# p1_main_ac_dc.net
KiCad netlist of a schematic drawn in Altium Designer
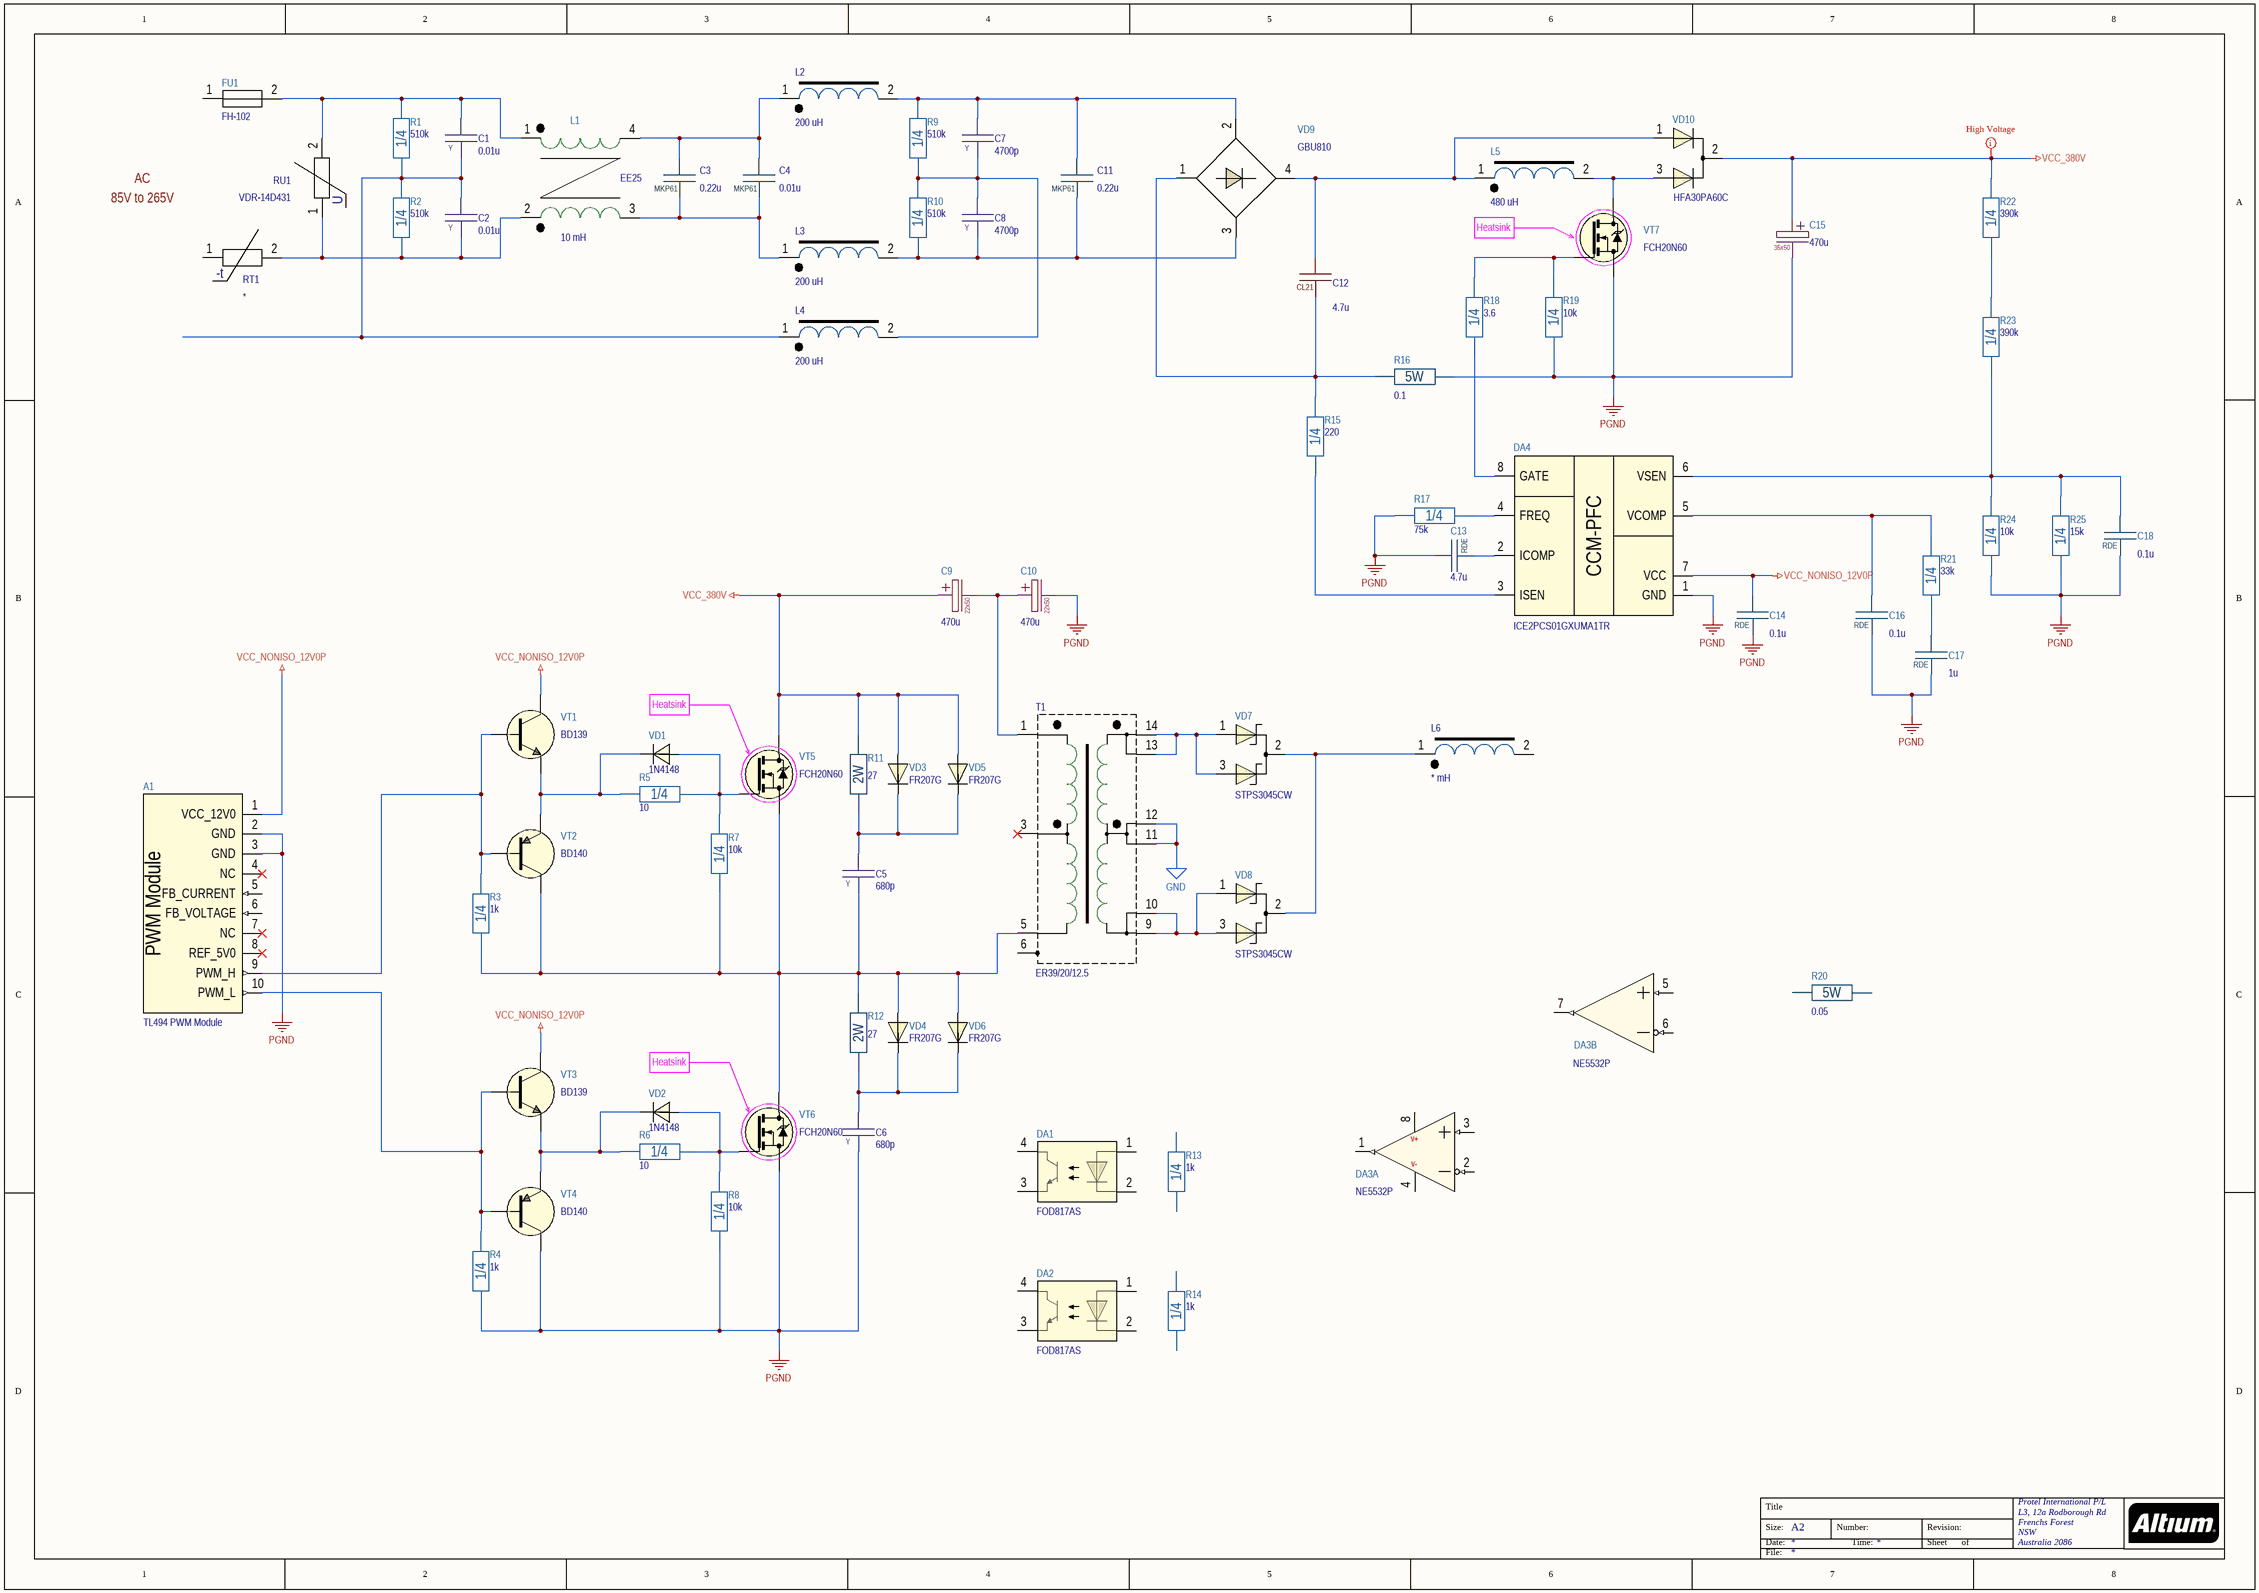
[diagram p0: p1_main_ac_dc.SchDoc]

(export (version "E")
  (design (tool "Eeschema 10.0.6"))
  (components
    (comp (ref "A1")
      (value "TL494 PWM Module")
      (footprint "PcbLib_Others:PWM-TL494")
      (libsource (lib "Schlib_OtherComponents") (part "PWM-MODULE"))
    )
    (comp (ref "C1")
      (value "0.01u")
      (footprint "PcbLib_RC:JYC_Y2_CAP_6.5")
      (description "High Voltage Ceramic Capacitor")
      (fields
        (field (name "TOLERANCE") "± 20 %")
        (field (name "VOLTAGE") "2000V")
        (field (name "PACKAGE") "Y")
      )
      (libsource (lib "Schlib_RC") (part "JB_Y2"))
    )
    (comp (ref "C2")
      (value "0.01u")
      (footprint "PcbLib_RC:JYC_Y2_CAP_6.5")
      (description "High Voltage Ceramic Capacitor")
      (fields
        (field (name "TOLERANCE") "± 20 %")
        (field (name "VOLTAGE") "2000V")
        (field (name "PACKAGE") "Y")
      )
      (libsource (lib "Schlib_RC") (part "JB_Y2"))
    )
    (comp (ref "C3")
      (value "0.22u")
      (footprint "PcbLib_RC:MKP61_18x14.5x8.5_P15")
      (description "Metallized Polypropylene Film Capacitor for high voltage application")
      (fields
        (field (name "TOLERANCE") "± 10 %")
        (field (name "VOLTAGE") "300V")
        (field (name "PACKAGE") "MKP61")
      )
      (libsource (lib "Schlib_RC") (part "MKP61"))
    )
    (comp (ref "C4")
      (value "0.01u")
      (footprint "PcbLib_RC:MKP61_18x12x6_P15")
      (description "Metallized Polypropylene Film Capacitor for high voltage application")
      (fields
        (field (name "TOLERANCE") "± 10 %")
        (field (name "VOLTAGE") "300V")
        (field (name "PACKAGE") "MKP61")
      )
      (libsource (lib "Schlib_RC") (part "MKP61"))
    )
    (comp (ref "C5")
      (value "680p")
      (footprint "PcbLib_RC:JYC_Y2_CAP_7.5")
      (description "High Voltage Ceramic Capacitor")
      (fields
        (field (name "TOLERANCE") "± 10 %")
        (field (name "VOLTAGE") "2000V")
        (field (name "PACKAGE") "Y")
      )
      (libsource (lib "Schlib_RC") (part "JB_Y2"))
    )
    (comp (ref "C6")
      (value "680p")
      (footprint "PcbLib_RC:JYC_Y2_CAP_7.5")
      (description "High Voltage Ceramic Capacitor")
      (fields
        (field (name "TOLERANCE") "± 10 %")
        (field (name "VOLTAGE") "2000V")
        (field (name "PACKAGE") "Y")
      )
      (libsource (lib "Schlib_RC") (part "JB_Y2"))
    )
    (comp (ref "C7")
      (value "4700p")
      (footprint "PcbLib_RC:JYC_Y2_CAP_6.5")
      (description "High Voltage Ceramic Capacitor")
      (fields
        (field (name "TOLERANCE") "± 20 %")
        (field (name "VOLTAGE") "2000V")
        (field (name "PACKAGE") "Y")
      )
      (libsource (lib "Schlib_RC") (part "JB_Y2"))
    )
    (comp (ref "C8")
      (value "4700p")
      (footprint "PcbLib_RC:JYC_Y2_CAP_6.5")
      (description "High Voltage Ceramic Capacitor")
      (fields
        (field (name "TOLERANCE") "± 20 %")
        (field (name "VOLTAGE") "2000V")
        (field (name "PACKAGE") "Y")
      )
      (libsource (lib "Schlib_RC") (part "JB_Y2"))
    )
    (comp (ref "C9")
      (value "470u")
      (footprint "PcbLib_RC:ECAP22X50X10")
      (description "Aluminium capacitors 35x50mm")
      (fields
        (field (name "TOLERANCE") "± 20 %")
        (field (name "VOLTAGE") "200V")
        (field (name "PACKAGE") "22x50")
      )
      (libsource (lib "Schlib_RC") (part "ECAP_22x50"))
    )
    (comp (ref "C10")
      (value "470u")
      (footprint "PcbLib_RC:ECAP22X50X10")
      (description "Aluminium capacitors 35x50mm")
      (fields
        (field (name "TOLERANCE") "± 20 %")
        (field (name "VOLTAGE") "200V")
        (field (name "PACKAGE") "22x50")
      )
      (libsource (lib "Schlib_RC") (part "ECAP_22x50"))
    )
    (comp (ref "C11")
      (value "0.22u")
      (footprint "PcbLib_RC:MKP61_18x14.5x8.5_P15")
      (description "Metallized Polypropylene Film Capacitor for high voltage application")
      (fields
        (field (name "TOLERANCE") "± 10 %")
        (field (name "VOLTAGE") "300V")
        (field (name "PACKAGE") "MKP61")
      )
      (libsource (lib "Schlib_RC") (part "MKP61"))
    )
    (comp (ref "C12")
      (value "4.7u")
      (footprint "PcbLib_RC:CL21_29x24.5x14.0_P27.5")
      (description "CL21 Type Metallized Polyester Film Capacitor")
      (fields
        (field (name "TOLERANCE") "± * %")
        (field (name "VOLTAGE") "630V")
        (field (name "PACKAGE") "CL21")
      )
      (libsource (lib "Schlib_RC") (part "CL21"))
    )
    (comp (ref "C13")
      (value "4.7u")
      (footprint "PcbLib_RC:RDE_2P1")
      (description "MLCC radial lead type with epoxy coat (RDE Series)")
      (fields
        (field (name "TOLERANCE") "± 10 %")
        (field (name "VOLTAGE") "50V")
        (field (name "PACKAGE") "RDE")
      )
      (libsource (lib "Schlib_RC") (part "RDE_CAP"))
    )
    (comp (ref "C14")
      (value "0.1u")
      (footprint "PcbLib_RC:RDE_1P1")
      (description "MLCC radial lead type with epoxy coat (RDE Series)")
      (fields
        (field (name "TOLERANCE") "± 10 %")
        (field (name "VOLTAGE") "100V")
        (field (name "PACKAGE") "RDE")
      )
      (libsource (lib "Schlib_RC") (part "RDE_CAP"))
    )
    (comp (ref "C15")
      (value "470u")
      (footprint "PcbLib_RC:ECAP35X50X10")
      (description "Aluminium capacitors 35x50mm")
      (fields
        (field (name "TOLERANCE") "± 20 %")
        (field (name "VOLTAGE") "450V")
        (field (name "PACKAGE") "35x50")
      )
      (libsource (lib "Schlib_RC") (part "ECAP_35x50"))
    )
    (comp (ref "C16")
      (value "0.1u")
      (footprint "PcbLib_RC:RDE_1P1")
      (description "MLCC radial lead type with epoxy coat (RDE Series)")
      (fields
        (field (name "TOLERANCE") "± 10 %")
        (field (name "VOLTAGE") "100V")
        (field (name "PACKAGE") "RDE")
      )
      (libsource (lib "Schlib_RC") (part "RDE_CAP"))
    )
    (comp (ref "C17")
      (value "1u")
      (footprint "PcbLib_RC:RDE_2P1")
      (description "MLCC radial lead type with epoxy coat (RDE Series)")
      (fields
        (field (name "TOLERANCE") "± 10 %")
        (field (name "VOLTAGE") "50V")
        (field (name "PACKAGE") "RDE")
      )
      (libsource (lib "Schlib_RC") (part "RDE_CAP"))
    )
    (comp (ref "C18")
      (value "0.1u")
      (footprint "PcbLib_RC:RDE_1P1")
      (description "MLCC radial lead type with epoxy coat (RDE Series)")
      (fields
        (field (name "TOLERANCE") "± 10 %")
        (field (name "VOLTAGE") "100V")
        (field (name "PACKAGE") "RDE")
      )
      (libsource (lib "Schlib_RC") (part "RDE_CAP"))
    )
    (comp (ref "DA1")
      (value "FOD817AS")
      (footprint "PcbLib_Others:N04C")
      (description "Optoisolator 5kV transistor")
      (fields (field (name "MANUFACTURER") "ON Semiconductor"))
      (libsource (lib "Schlib_ONSemiconductor") (part "FOD817AS"))
    )
    (comp (ref "DA2")
      (value "FOD817AS")
      (footprint "PcbLib_Others:N04C")
      (description "Optoisolator 5kV transistor")
      (fields (field (name "MANUFACTURER") "ON Semiconductor"))
      (libsource (lib "Schlib_ONSemiconductor") (part "FOD817AS"))
    )
    (comp (ref "DA3")
      (value "NE5532P")
      (footprint "PcbLib_ICs:DIP-8P-M01")
      (description "DUAL LOW-NOISE OPERATIONAL AMPLIFIERS")
      (fields (field (name "MANUFACTURER") "Texas Instruments"))
      (libsource (lib "Schlib_Texas_Instruments") (part "NE5532P"))
    )
    (comp (ref "DA4")
      (value "ICE2PCS01GXUMA1TR")
      (footprint "PcbLib_ICs:SOIC-8_with_DIP-8")
      (description "PFC Controller in Continuous Conduction Mode")
      (fields (field (name "MANUFACTURER") "Infineon"))
      (libsource (lib "Schlib_Infineon") (part "ICE2PCS01GXUMA1TR"))
    )
    (comp (ref "FU1")
      (value "FH-102")
      (footprint "PcbLib_Others:FH-102")
      (description "Fuse holder 5.2х20mm")
      (libsource (lib "Schlib_OtherComponents") (part "FH-102"))
    )
    (comp (ref "L1")
      (value "10 mH")
      (footprint "PcbLib_Others:EE25/10/6")
      (description "EE25 Ferrite Core inductor")
      (fields (field (name "CORE") "EE25"))
      (libsource (lib "Schlib_OtherComponents") (part "EE25"))
    )
    (comp (ref "L2")
      (value "200 uH")
      (footprint "PcbLib_RC:CORE_D20_GB")
      (description "Ferrite Core D20.3/12.7/6.35 mm")
      (libsource (lib "Schlib_OtherComponents") (part "CORE_D20"))
    )
    (comp (ref "L3")
      (value "200 uH")
      (footprint "PcbLib_RC:CORE_D20_GB")
      (description "Ferrite Core D20.3/12.7/6.35 mm")
      (libsource (lib "Schlib_OtherComponents") (part "CORE_D20"))
    )
    (comp (ref "L4")
      (value "200 uH")
      (footprint "PcbLib_RC:CORE_D20_GB")
      (description "Ferrite Core D20.3/12.7/6.35 mm")
      (libsource (lib "Schlib_OtherComponents") (part "CORE_D20"))
    )
    (comp (ref "L5")
      (value "480 uH")
      (footprint "PcbLib_RC:CORE_D36_GB")
      (description "Ferrite Core D35.8/22.4/10.5 mm")
      (libsource (lib "Schlib_OtherComponents") (part "CORE_D36"))
    )
    (comp (ref "L6")
      (value "* mH")
      (footprint "PcbLib_RC:CORE_D33_GB")
      (description "Ferrite Core D32.8/20.1/10.7 mm")
      (libsource (lib "Schlib_OtherComponents") (part "CORE_D33"))
    )
    (comp (ref "R1")
      (value "510k")
      (footprint "PcbLib_RC:CFR-25")
      (description "Resistor 1/4W")
      (fields
        (field (name "TOLERANCE") "± 1 %")
        (field (name "PART NUMBER") "MFR-25FTF52-510K")
        (field (name "PACKAGE") "1/4")
      )
      (libsource (lib "Schlib_RC") (part "CF25"))
    )
    (comp (ref "R2")
      (value "510k")
      (footprint "PcbLib_RC:CFR-25")
      (description "Resistor 1/4W")
      (fields
        (field (name "TOLERANCE") "± 1 %")
        (field (name "PART NUMBER") "MFR-25FTF52-510K")
        (field (name "PACKAGE") "1/4")
      )
      (libsource (lib "Schlib_RC") (part "CF25"))
    )
    (comp (ref "R3")
      (value "1k")
      (footprint "PcbLib_RC:CFR-25")
      (description "Resistor 1/4W")
      (fields
        (field (name "TOLERANCE") "± 1 %")
        (field (name "PART NUMBER") "MFR-25FTF52-1K")
        (field (name "PACKAGE") "1/4")
      )
      (libsource (lib "Schlib_RC") (part "CF25"))
    )
    (comp (ref "R4")
      (value "1k")
      (footprint "PcbLib_RC:CFR-25")
      (description "Resistor 1/4W")
      (fields
        (field (name "TOLERANCE") "± 1 %")
        (field (name "PART NUMBER") "MFR-25FTF52-1K")
        (field (name "PACKAGE") "1/4")
      )
      (libsource (lib "Schlib_RC") (part "CF25"))
    )
    (comp (ref "R5")
      (value "10")
      (footprint "PcbLib_RC:CFR-25(VERTICAL)")
      (description "Resistor 1/4W")
      (fields
        (field (name "TOLERANCE") "± 1 %")
        (field (name "PART NUMBER") "MFR-25FTF52-10R")
        (field (name "PACKAGE") "1/4")
      )
      (libsource (lib "Schlib_RC") (part "CF25"))
    )
    (comp (ref "R6")
      (value "10")
      (footprint "PcbLib_RC:CFR-25(VERTICAL)")
      (description "Resistor 1/4W")
      (fields
        (field (name "TOLERANCE") "± 1 %")
        (field (name "PART NUMBER") "MFR-25FTF52-10R")
        (field (name "PACKAGE") "1/4")
      )
      (libsource (lib "Schlib_RC") (part "CF25"))
    )
    (comp (ref "R7")
      (value "10k")
      (footprint "PcbLib_RC:CFR-25")
      (description "Resistor 1/4W")
      (fields
        (field (name "TOLERANCE") "± 1 %")
        (field (name "PART NUMBER") "MFR-25FTF52-10K")
        (field (name "PACKAGE") "1/4")
      )
      (libsource (lib "Schlib_RC") (part "CF25"))
    )
    (comp (ref "R8")
      (value "10k")
      (footprint "PcbLib_RC:CFR-25")
      (description "Resistor 1/4W")
      (fields
        (field (name "TOLERANCE") "± 1 %")
        (field (name "PART NUMBER") "MFR-25FTF52-10K")
        (field (name "PACKAGE") "1/4")
      )
      (libsource (lib "Schlib_RC") (part "CF25"))
    )
    (comp (ref "R9")
      (value "510k")
      (footprint "PcbLib_RC:CFR-25")
      (description "Resistor 1/4W")
      (fields
        (field (name "TOLERANCE") "± 1 %")
        (field (name "PART NUMBER") "MFR-25FTF52-510K")
        (field (name "PACKAGE") "1/4")
      )
      (libsource (lib "Schlib_RC") (part "CF25"))
    )
    (comp (ref "R10")
      (value "510k")
      (footprint "PcbLib_RC:CFR-25")
      (description "Resistor 1/4W")
      (fields
        (field (name "TOLERANCE") "± 1 %")
        (field (name "PART NUMBER") "MFR-25FTF52-510K")
        (field (name "PACKAGE") "1/4")
      )
      (libsource (lib "Schlib_RC") (part "CF25"))
    )
    (comp (ref "R11")
      (value "27")
      (footprint "PcbLib_RC:CFR-200")
      (description "Resistor 2W")
      (fields
        (field (name "TOLERANCE") "± 5 %")
        (field (name "PART NUMBER") "KNP200JB-73-27R")
        (field (name "PACKAGE") "2W")
      )
      (libsource (lib "Schlib_RC") (part "CF200"))
    )
    (comp (ref "R12")
      (value "27")
      (footprint "PcbLib_RC:CFR-200")
      (description "Resistor 2W")
      (fields
        (field (name "TOLERANCE") "± 5 %")
        (field (name "PART NUMBER") "KNP200JB-73-27R")
        (field (name "PACKAGE") "2W")
      )
      (libsource (lib "Schlib_RC") (part "CF200"))
    )
    (comp (ref "R13")
      (value "1k")
      (footprint "PcbLib_RC:CFR-25")
      (description "Resistor 1/4W")
      (fields
        (field (name "TOLERANCE") "± 1 %")
        (field (name "PART NUMBER") "MFR-25FTF52-1K")
        (field (name "PACKAGE") "1/4")
      )
      (libsource (lib "Schlib_RC") (part "CF25"))
    )
    (comp (ref "R14")
      (value "1k")
      (footprint "PcbLib_RC:CFR-25")
      (description "Resistor 1/4W")
      (fields
        (field (name "TOLERANCE") "± 1 %")
        (field (name "PART NUMBER") "MFR-25FTF52-1K")
        (field (name "PACKAGE") "1/4")
      )
      (libsource (lib "Schlib_RC") (part "CF25"))
    )
    (comp (ref "R15")
      (value "220")
      (footprint "PcbLib_RC:CFR-25")
      (description "Resistor 1/4W")
      (fields
        (field (name "TOLERANCE") "± 1 %")
        (field (name "PART NUMBER") "MFR-25FTF52-220R")
        (field (name "PACKAGE") "1/4")
      )
      (libsource (lib "Schlib_RC") (part "CF25"))
    )
    (comp (ref "R16")
      (value "0.1")
      (footprint "PcbLib_RC:BPR58")
      (description "Rectangular type metal plate resistors")
      (fields
        (field (name "TOLERANCE") "± 5 %")
        (field (name "PART NUMBER") "BPR58CR10J")
        (field (name "PACKAGE") "5W")
      )
      (libsource (lib "Schlib_RC") (part "BPR58"))
    )
    (comp (ref "R17")
      (value "75k")
      (footprint "PcbLib_RC:CFR-25")
      (description "Resistor 1/4W")
      (fields
        (field (name "TOLERANCE") "± 1 %")
        (field (name "PART NUMBER") "MFR-25FTF52-75K")
        (field (name "PACKAGE") "1/4")
      )
      (libsource (lib "Schlib_RC") (part "CF25"))
    )
    (comp (ref "R18")
      (value "3.6")
      (footprint "PcbLib_RC:CFR-25")
      (description "Resistor 1/4W")
      (fields
        (field (name "TOLERANCE") "± 1 %")
        (field (name "PART NUMBER") "MFR-25FTF52-3R6")
        (field (name "PACKAGE") "1/4")
      )
      (libsource (lib "Schlib_RC") (part "CF25"))
    )
    (comp (ref "R19")
      (value "10k")
      (footprint "PcbLib_RC:CFR-25")
      (description "Resistor 1/4W")
      (fields
        (field (name "TOLERANCE") "± 1 %")
        (field (name "PART NUMBER") "MFR-25FTF52-10K")
        (field (name "PACKAGE") "1/4")
      )
      (libsource (lib "Schlib_RC") (part "CF25"))
    )
    (comp (ref "R20")
      (value "0.05")
      (footprint "PcbLib_RC:BPR58")
      (description "Rectangular type metal plate resistors")
      (fields
        (field (name "TOLERANCE") "± 10 %")
        (field (name "PART NUMBER") "BPR58C50LK")
        (field (name "PACKAGE") "5W")
      )
      (libsource (lib "Schlib_RC") (part "BPR58"))
    )
    (comp (ref "R21")
      (value "33k")
      (footprint "PcbLib_RC:CFR-25")
      (description "Resistor 1/4W")
      (fields
        (field (name "TOLERANCE") "± 1 %")
        (field (name "PART NUMBER") "MFR-25FTF52-33K")
        (field (name "PACKAGE") "1/4")
      )
      (libsource (lib "Schlib_RC") (part "CF25"))
    )
    (comp (ref "R22")
      (value "390k")
      (footprint "PcbLib_RC:CFR-25")
      (description "Resistor 1/4W")
      (fields
        (field (name "TOLERANCE") "± 1 %")
        (field (name "PART NUMBER") "MFR-25FTF52-390K")
        (field (name "PACKAGE") "1/4")
      )
      (libsource (lib "Schlib_RC") (part "CF25"))
    )
    (comp (ref "R23")
      (value "390k")
      (footprint "PcbLib_RC:CFR-25")
      (description "Resistor 1/4W")
      (fields
        (field (name "TOLERANCE") "± 1 %")
        (field (name "PART NUMBER") "MFR-25FTF52-390K")
        (field (name "PACKAGE") "1/4")
      )
      (libsource (lib "Schlib_RC") (part "CF25"))
    )
    (comp (ref "R24")
      (value "10k")
      (footprint "PcbLib_RC:CFR-25")
      (description "Resistor 1/4W")
      (fields
        (field (name "TOLERANCE") "± 1 %")
        (field (name "PART NUMBER") "MFR-25FTF52-10K")
        (field (name "PACKAGE") "1/4")
      )
      (libsource (lib "Schlib_RC") (part "CF25"))
    )
    (comp (ref "R25")
      (value "15k")
      (footprint "PcbLib_RC:CFR-25")
      (description "Resistor 1/4W")
      (fields
        (field (name "TOLERANCE") "± 1 %")
        (field (name "PART NUMBER") "MFR-25FTF52-15K")
        (field (name "PACKAGE") "1/4")
      )
      (libsource (lib "Schlib_RC") (part "CF25"))
    )
    (comp (ref "RT1")
      (value "*")
      (footprint "PcbLib_Others:NTC_D10")
      (description "NTC thermistors")
      (libsource (lib "Schlib_OtherComponents") (part "NTC"))
    )
    (comp (ref "RU1")
      (value "VDR-14D431")
      (footprint "PcbLib_Others:VARISTOR_14D")
      (description "Varistor")
      (libsource (lib "Schlib_OtherComponents") (part "VARISTOR"))
    )
    (comp (ref "T1")
      (value "ER39/20/12.5")
      (footprint "PcbLib_Others:ER39/20/12.5")
      (description "EE39 Ferrite Core, with footprint for ER35, EE33, EI33 etc.")
      (libsource (lib "Schlib_OtherComponents") (part "ER39"))
    )
    (comp (ref "VD1")
      (value "1N4148")
      (footprint "PcbLib_Discrete:DO-35 GLASS LIGHT RED")
      (description "High-speed diode")
      (libsource (lib "Schlib_NXP_Semiconductors") (part "1N4148"))
    )
    (comp (ref "VD2")
      (value "1N4148")
      (footprint "PcbLib_Discrete:DO-35 GLASS LIGHT RED")
      (description "High-speed diode")
      (libsource (lib "Schlib_NXP_Semiconductors") (part "1N4148"))
    )
    (comp (ref "VD3")
      (value "FR207G")
      (footprint "PcbLib_Discrete:DO-15")
      (description "Diode 2A, 1000V Glass Passivated Fast Recovery Rectifiers")
      (fields (field (name "MANUFACTURER") "Taiwan Semiconductor Corporation"))
      (libsource (lib "Schlib_Taiwan_Semiconductor") (part "FR207G"))
    )
    (comp (ref "VD4")
      (value "FR207G")
      (footprint "PcbLib_Discrete:DO-15")
      (description "Diode 2A, 1000V Glass Passivated Fast Recovery Rectifiers")
      (fields (field (name "MANUFACTURER") "Taiwan Semiconductor Corporation"))
      (libsource (lib "Schlib_Taiwan_Semiconductor") (part "FR207G"))
    )
    (comp (ref "VD5")
      (value "FR207G")
      (footprint "PcbLib_Discrete:DO-15")
      (description "Diode 2A, 1000V Glass Passivated Fast Recovery Rectifiers")
      (fields (field (name "MANUFACTURER") "Taiwan Semiconductor Corporation"))
      (libsource (lib "Schlib_Taiwan_Semiconductor") (part "FR207G"))
    )
    (comp (ref "VD6")
      (value "FR207G")
      (footprint "PcbLib_Discrete:DO-15")
      (description "Diode 2A, 1000V Glass Passivated Fast Recovery Rectifiers")
      (fields (field (name "MANUFACTURER") "Taiwan Semiconductor Corporation"))
      (libsource (lib "Schlib_Taiwan_Semiconductor") (part "FR207G"))
    )
    (comp (ref "VD7")
      (value "STPS3045CW")
      (footprint "PcbLib_ICs:TO-247_with_TO-220 (VERTICAL)")
      (description "Power Schottky Rectifier Diode 45V, 2x15A")
      (fields (field (name "MANUFACTURER") "STMicroelectronics"))
      (libsource (lib "Schlib_STMicroelectronics") (part "STPS3045CW"))
    )
    (comp (ref "VD8")
      (value "STPS3045CW")
      (footprint "PcbLib_ICs:TO-247_with_TO-220 (VERTICAL)")
      (description "Power Schottky Rectifier Diode 45V, 2x15A")
      (fields (field (name "MANUFACTURER") "STMicroelectronics"))
      (libsource (lib "Schlib_STMicroelectronics") (part "STPS3045CW"))
    )
    (comp (ref "VD9")
      (value "GBU810")
      (footprint "PcbLib_Discrete:GBU810")
      (description "8A single phase bridge rectifier")
      (fields (field (name "MANUFACTURER") "Diodes Incorporated"))
      (libsource (lib "Schlib_OtherComponents") (part "GBU810"))
    )
    (comp (ref "VD10")
      (value "HFA30PA60C")
      (footprint "PcbLib_ICs:TO-247 ((HORIZONTAL, BOTTOM)")
      (description "Ultrafast, Soft Recovery Diode 600V, 15A")
      (fields (field (name "MANUFACTURER") "Infineon"))
      (libsource (lib "Schlib_Infineon") (part "HFA30PA60C"))
    )
    (comp (ref "VT1")
      (value "BD139")
      (footprint "PcbLib_ICs:TO-126 (VERTICAL)")
      (description "General Purpose n-p-n Transistors")
      (fields (field (name "MANUFACTURER") "STMicroelectronics"))
      (libsource (lib "Schlib_STMicroelectronics") (part "BD139"))
    )
    (comp (ref "VT2")
      (value "BD140")
      (footprint "PcbLib_ICs:TO-126 (VERTICAL)")
      (description "General Purpose p-n-p Transistors")
      (fields (field (name "MANUFACTURER") "STMicroelectronics"))
      (libsource (lib "Schlib_STMicroelectronics") (part "BD140"))
    )
    (comp (ref "VT3")
      (value "BD139")
      (footprint "PcbLib_ICs:TO-126 (VERTICAL)")
      (description "General Purpose n-p-n Transistors")
      (fields (field (name "MANUFACTURER") "STMicroelectronics"))
      (libsource (lib "Schlib_STMicroelectronics") (part "BD139"))
    )
    (comp (ref "VT4")
      (value "BD140")
      (footprint "PcbLib_ICs:TO-126 (VERTICAL)")
      (description "General Purpose p-n-p Transistors")
      (fields (field (name "MANUFACTURER") "STMicroelectronics"))
      (libsource (lib "Schlib_STMicroelectronics") (part "BD140"))
    )
    (comp (ref "VT5")
      (value "FCH20N60")
      (footprint "PcbLib_ICs:TO-247_with_TO-220 (VERTICAL)")
      (description "600V @ 20A N-Channel MOSFET")
      (fields (field (name "MANUFACTURER") "ON Semiconductor"))
      (libsource (lib "Schlib_ONSemiconductor") (part "FCH20N60"))
    )
    (comp (ref "VT6")
      (value "FCH20N60")
      (footprint "PcbLib_ICs:TO-247_with_TO-220 (VERTICAL)")
      (description "600V @ 20A N-Channel MOSFET")
      (fields (field (name "MANUFACTURER") "ON Semiconductor"))
      (libsource (lib "Schlib_ONSemiconductor") (part "FCH20N60"))
    )
    (comp (ref "VT7")
      (value "FCH20N60")
      (footprint "PcbLib_ICs:TO-247_with_TO-220 (VERTICAL)")
      (description "600V @ 20A N-Channel MOSFET")
      (fields (field (name "MANUFACTURER") "ON Semiconductor"))
      (libsource (lib "Schlib_ONSemiconductor") (part "FCH20N60"))
    )
  )
  (nets
    (net (code "1") (name "GND") (class "Default")
      (node (ref "T1") (pin "11") (pinfunction "11_11") (pintype "passive"))
      (node (ref "T1") (pin "12") (pinfunction "12_12") (pintype "passive"))
    )
    (net (code "2") (name "Net-(A1-PWM_H)") (class "Default")
      (node (ref "A1") (pin "9") (pinfunction "PWM_H_9") (pintype "output"))
      (node (ref "R3") (pin "2") (pinfunction "2_2") (pintype "passive"))
      (node (ref "VT1") (pin "1") (pinfunction "B_1") (pintype "passive"))
      (node (ref "VT2") (pin "1") (pinfunction "B_1") (pintype "passive"))
    )
    (net (code "3") (name "Net-(A1-PWM_L)") (class "Default")
      (node (ref "A1") (pin "10") (pinfunction "PWM_L_10") (pintype "output"))
      (node (ref "R4") (pin "2") (pinfunction "2_2") (pintype "passive"))
      (node (ref "VT3") (pin "1") (pinfunction "B_1") (pintype "passive"))
      (node (ref "VT4") (pin "1") (pinfunction "B_1") (pintype "passive"))
    )
    (net (code "4") (name "Net-(C1-Pad1)") (class "Default")
      (node (ref "C1") (pin "1") (pinfunction "1_1") (pintype "passive"))
      (node (ref "FU1") (pin "2") (pinfunction "2_2") (pintype "passive"))
      (node (ref "L1") (pin "1") (pinfunction "1_1") (pintype "passive"))
      (node (ref "R1") (pin "2") (pinfunction "2_2") (pintype "passive"))
      (node (ref "RU1") (pin "2") (pinfunction "2_2") (pintype "passive"))
    )
    (net (code "5") (name "Net-(C1-Pad2)") (class "Default")
      (node (ref "C1") (pin "2") (pinfunction "2_2") (pintype "passive"))
      (node (ref "C2") (pin "1") (pinfunction "1_1") (pintype "passive"))
      (node (ref "L4") (pin "1") (pinfunction "1_1") (pintype "passive"))
      (node (ref "R1") (pin "1") (pinfunction "1_1") (pintype "passive"))
      (node (ref "R2") (pin "2") (pinfunction "2_2") (pintype "passive"))
    )
    (net (code "6") (name "Net-(C2-Pad2)") (class "Default")
      (node (ref "C2") (pin "2") (pinfunction "2_2") (pintype "passive"))
      (node (ref "L1") (pin "2") (pinfunction "2_2") (pintype "passive"))
      (node (ref "R2") (pin "1") (pinfunction "1_1") (pintype "passive"))
      (node (ref "RT1") (pin "2") (pinfunction "2_2") (pintype "passive"))
      (node (ref "RU1") (pin "1") (pinfunction "1_1") (pintype "passive"))
    )
    (net (code "7") (name "Net-(C3-Pad1)") (class "Default")
      (node (ref "C3") (pin "1") (pinfunction "1_1") (pintype "passive"))
      (node (ref "C4") (pin "1") (pinfunction "1_1") (pintype "passive"))
      (node (ref "L1") (pin "3") (pinfunction "3_3") (pintype "passive"))
      (node (ref "L3") (pin "1") (pinfunction "1_1") (pintype "passive"))
    )
    (net (code "8") (name "Net-(C3-Pad2)") (class "Default")
      (node (ref "C3") (pin "2") (pinfunction "2_2") (pintype "passive"))
      (node (ref "C4") (pin "2") (pinfunction "2_2") (pintype "passive"))
      (node (ref "L1") (pin "4") (pinfunction "4_4") (pintype "passive"))
      (node (ref "L2") (pin "1") (pinfunction "1_1") (pintype "passive"))
    )
    (net (code "9") (name "Net-(C7-Pad2)") (class "Default")
      (node (ref "C7") (pin "2") (pinfunction "2_2") (pintype "passive"))
      (node (ref "C8") (pin "1") (pinfunction "1_1") (pintype "passive"))
      (node (ref "L4") (pin "2") (pinfunction "2_2") (pintype "passive"))
      (node (ref "R10") (pin "2") (pinfunction "2_2") (pintype "passive"))
      (node (ref "R9") (pin "1") (pinfunction "1_1") (pintype "passive"))
    )
    (net (code "10") (name "Net-(C10-Pad1)") (class "Default")
      (node (ref "C10") (pin "1") (pinfunction "1_1") (pintype "passive"))
      (node (ref "C9") (pin "2") (pinfunction "2_2") (pintype "passive"))
      (node (ref "T1") (pin "1") (pinfunction "1_1") (pintype "passive"))
    )
    (net (code "11") (name "Net-(C17-Pad1)") (class "Default")
      (node (ref "C17") (pin "1") (pinfunction "1_1") (pintype "passive"))
      (node (ref "R21") (pin "1") (pinfunction "1_1") (pintype "passive"))
    )
    (net (code "12") (name "Net-(DA4-FREQ)") (class "Default")
      (node (ref "DA4") (pin "4") (pinfunction "FREQ_4") (pintype "passive"))
      (node (ref "R17") (pin "1") (pinfunction "1_1") (pintype "passive"))
    )
    (net (code "13") (name "Net-(DA4-GATE)") (class "Default")
      (node (ref "DA4") (pin "8") (pinfunction "GATE_8") (pintype "passive"))
      (node (ref "R18") (pin "1") (pinfunction "1_1") (pintype "passive"))
    )
    (net (code "14") (name "Net-(DA4-ICOMP)") (class "Default")
      (node (ref "C13") (pin "2") (pinfunction "2_2") (pintype "passive"))
      (node (ref "DA4") (pin "2") (pinfunction "ICOMP_2") (pintype "passive"))
    )
    (net (code "15") (name "Net-(DA4-ISEN)") (class "Default")
      (node (ref "DA4") (pin "3") (pinfunction "ISEN_3") (pintype "passive"))
      (node (ref "R15") (pin "1") (pinfunction "1_1") (pintype "passive"))
    )
    (net (code "16") (name "Net-(DA4-VCOMP)") (class "Default")
      (node (ref "C16") (pin "1") (pinfunction "1_1") (pintype "passive"))
      (node (ref "DA4") (pin "5") (pinfunction "VCOMP_5") (pintype "passive"))
      (node (ref "R21") (pin "2") (pinfunction "2_2") (pintype "passive"))
    )
    (net (code "17") (name "Net-(DA4-VSEN)") (class "Default")
      (node (ref "C18") (pin "1") (pinfunction "1_1") (pintype "passive"))
      (node (ref "DA4") (pin "6") (pinfunction "VSEN_6") (pintype "passive"))
      (node (ref "R23") (pin "1") (pinfunction "1_1") (pintype "passive"))
      (node (ref "R24") (pin "2") (pinfunction "2_2") (pintype "passive"))
      (node (ref "R25") (pin "2") (pinfunction "2_2") (pintype "passive"))
    )
    (net (code "18") (name "Net-(R22-Pad1)") (class "Default")
      (node (ref "R22") (pin "1") (pinfunction "1_1") (pintype "passive"))
      (node (ref "R23") (pin "2") (pinfunction "2_2") (pintype "passive"))
    )
    (net (code "19") (name "Net-(VD3-C)") (class "Default")
      (node (ref "C5") (pin "2") (pinfunction "2_2") (pintype "passive"))
      (node (ref "R11") (pin "1") (pinfunction "1_1") (pintype "passive"))
      (node (ref "VD3") (pin "1") (pinfunction "C_1") (pintype "passive"))
      (node (ref "VD5") (pin "1") (pinfunction "C_1") (pintype "passive"))
    )
    (net (code "20") (name "Net-(VD4-A)") (class "Default")
      (node (ref "C5") (pin "1") (pinfunction "1_1") (pintype "passive"))
      (node (ref "R12") (pin "2") (pinfunction "2_2") (pintype "passive"))
      (node (ref "R3") (pin "1") (pinfunction "1_1") (pintype "passive"))
      (node (ref "R7") (pin "1") (pinfunction "1_1") (pintype "passive"))
      (node (ref "T1") (pin "5") (pinfunction "5_5") (pintype "passive"))
      (node (ref "VD4") (pin "2") (pinfunction "A_2") (pintype "passive"))
      (node (ref "VD6") (pin "2") (pinfunction "A_2") (pintype "passive"))
      (node (ref "VT2") (pin "2") (pinfunction "C_2") (pintype "passive"))
      (node (ref "VT5") (pin "3") (pinfunction "S_3") (pintype "passive"))
      (node (ref "VT6") (pin "2") (pinfunction "D_2") (pintype "passive"))
    )
    (net (code "21") (name "Net-(VD4-C)") (class "Default")
      (node (ref "C6") (pin "2") (pinfunction "2_2") (pintype "passive"))
      (node (ref "R12") (pin "1") (pinfunction "1_1") (pintype "passive"))
      (node (ref "VD4") (pin "1") (pinfunction "C_1") (pintype "passive"))
      (node (ref "VD6") (pin "1") (pinfunction "C_1") (pintype "passive"))
    )
    (net (code "22") (name "Net-(VD7-A1)") (class "Default")
      (node (ref "T1") (pin "13") (pinfunction "13_13") (pintype "passive"))
      (node (ref "T1") (pin "14") (pinfunction "14_14") (pintype "passive"))
      (node (ref "VD7") (pin "1") (pinfunction "A1_1") (pintype "passive"))
      (node (ref "VD7") (pin "3") (pinfunction "A2_3") (pintype "passive"))
    )
    (net (code "23") (name "Net-(VD7-C)") (class "Default")
      (node (ref "L6") (pin "1") (pinfunction "1_1") (pintype "passive"))
      (node (ref "VD7") (pin "2") (pinfunction "C_2") (pintype "passive"))
      (node (ref "VD8") (pin "2") (pinfunction "C_2") (pintype "passive"))
    )
    (net (code "24") (name "Net-(VD8-A1)") (class "Default")
      (node (ref "T1") (pin "10") (pinfunction "10_10") (pintype "passive"))
      (node (ref "T1") (pin "9") (pinfunction "9_9") (pintype "passive"))
      (node (ref "VD8") (pin "1") (pinfunction "A1_1") (pintype "passive"))
      (node (ref "VD8") (pin "3") (pinfunction "A2_3") (pintype "passive"))
    )
    (net (code "25") (name "Net-(VD9-AC1)") (class "Default")
      (node (ref "C11") (pin "2") (pinfunction "2_2") (pintype "passive"))
      (node (ref "C7") (pin "1") (pinfunction "1_1") (pintype "passive"))
      (node (ref "L2") (pin "2") (pinfunction "2_2") (pintype "passive"))
      (node (ref "R9") (pin "2") (pinfunction "2_2") (pintype "passive"))
      (node (ref "VD9") (pin "2") (pinfunction "AC1_2") (pintype "passive"))
    )
    (net (code "26") (name "Net-(VD9-AC2)") (class "Default")
      (node (ref "C11") (pin "1") (pinfunction "1_1") (pintype "passive"))
      (node (ref "C8") (pin "2") (pinfunction "2_2") (pintype "passive"))
      (node (ref "L3") (pin "2") (pinfunction "2_2") (pintype "passive"))
      (node (ref "R10") (pin "1") (pinfunction "1_1") (pintype "passive"))
      (node (ref "VD9") (pin "3") (pinfunction "AC2_3") (pintype "passive"))
    )
    (net (code "27") (name "Net-(VD9-M)") (class "Default")
      (node (ref "C12") (pin "1") (pinfunction "1_1") (pintype "passive"))
      (node (ref "R15") (pin "2") (pinfunction "2_2") (pintype "passive"))
      (node (ref "R16") (pin "1") (pinfunction "1_1") (pintype "passive"))
      (node (ref "VD9") (pin "1") (pinfunction "M_1") (pintype "passive"))
    )
    (net (code "28") (name "Net-(VD10-A1)") (class "Default")
      (node (ref "C12") (pin "2") (pinfunction "2_2") (pintype "passive"))
      (node (ref "L5") (pin "1") (pinfunction "1_1") (pintype "passive"))
      (node (ref "VD10") (pin "1") (pinfunction "A1_1") (pintype "passive"))
      (node (ref "VD9") (pin "4") (pinfunction "P_4") (pintype "passive"))
    )
    (net (code "29") (name "Net-(VD10-A2)") (class "Default")
      (node (ref "L5") (pin "2") (pinfunction "2_2") (pintype "passive"))
      (node (ref "VD10") (pin "3") (pinfunction "A2_3") (pintype "passive"))
      (node (ref "VT7") (pin "2") (pinfunction "D_2") (pintype "passive"))
    )
    (net (code "30") (name "Net-(VT1-E)") (class "Default")
      (node (ref "R5") (pin "2") (pinfunction "2_2") (pintype "passive"))
      (node (ref "VD1") (pin "1") (pinfunction "1_1") (pintype "passive"))
      (node (ref "VT1") (pin "3") (pinfunction "E_3") (pintype "passive"))
      (node (ref "VT2") (pin "3") (pinfunction "E_3") (pintype "passive"))
    )
    (net (code "31") (name "Net-(VT3-E)") (class "Default")
      (node (ref "R6") (pin "2") (pinfunction "2_2") (pintype "passive"))
      (node (ref "VD2") (pin "1") (pinfunction "1_1") (pintype "passive"))
      (node (ref "VT3") (pin "3") (pinfunction "E_3") (pintype "passive"))
      (node (ref "VT4") (pin "3") (pinfunction "E_3") (pintype "passive"))
    )
    (net (code "32") (name "Net-(VT5-G)") (class "Default")
      (node (ref "R5") (pin "1") (pinfunction "1_1") (pintype "passive"))
      (node (ref "R7") (pin "2") (pinfunction "2_2") (pintype "passive"))
      (node (ref "VD1") (pin "2") (pinfunction "2_2") (pintype "passive"))
      (node (ref "VT5") (pin "1") (pinfunction "G_1") (pintype "passive"))
    )
    (net (code "33") (name "Net-(VT6-G)") (class "Default")
      (node (ref "R6") (pin "1") (pinfunction "1_1") (pintype "passive"))
      (node (ref "R8") (pin "2") (pinfunction "2_2") (pintype "passive"))
      (node (ref "VD2") (pin "2") (pinfunction "2_2") (pintype "passive"))
      (node (ref "VT6") (pin "1") (pinfunction "G_1") (pintype "passive"))
    )
    (net (code "34") (name "Net-(VT7-G)") (class "Default")
      (node (ref "R18") (pin "2") (pinfunction "2_2") (pintype "passive"))
      (node (ref "R19") (pin "2") (pinfunction "2_2") (pintype "passive"))
      (node (ref "VT7") (pin "1") (pinfunction "G_1") (pintype "passive"))
    )
    (net (code "35") (name "PGND") (class "Default")
      (node (ref "A1") (pin "2") (pinfunction "GND_2") (pintype "passive"))
      (node (ref "A1") (pin "3") (pinfunction "GND_3") (pintype "passive"))
      (node (ref "C10") (pin "2") (pinfunction "2_2") (pintype "passive"))
      (node (ref "C13") (pin "1") (pinfunction "1_1") (pintype "passive"))
      (node (ref "C14") (pin "2") (pinfunction "2_2") (pintype "passive"))
      (node (ref "C15") (pin "2") (pinfunction "2_2") (pintype "passive"))
      (node (ref "C16") (pin "2") (pinfunction "2_2") (pintype "passive"))
      (node (ref "C17") (pin "2") (pinfunction "2_2") (pintype "passive"))
      (node (ref "C18") (pin "2") (pinfunction "2_2") (pintype "passive"))
      (node (ref "C6") (pin "1") (pinfunction "1_1") (pintype "passive"))
      (node (ref "DA4") (pin "1") (pinfunction "GND_1") (pintype "passive"))
      (node (ref "R16") (pin "2") (pinfunction "2_2") (pintype "passive"))
      (node (ref "R17") (pin "2") (pinfunction "2_2") (pintype "passive"))
      (node (ref "R19") (pin "1") (pinfunction "1_1") (pintype "passive"))
      (node (ref "R24") (pin "1") (pinfunction "1_1") (pintype "passive"))
      (node (ref "R25") (pin "1") (pinfunction "1_1") (pintype "passive"))
      (node (ref "R4") (pin "1") (pinfunction "1_1") (pintype "passive"))
      (node (ref "R8") (pin "1") (pinfunction "1_1") (pintype "passive"))
      (node (ref "VT4") (pin "2") (pinfunction "C_2") (pintype "passive"))
      (node (ref "VT6") (pin "3") (pinfunction "S_3") (pintype "passive"))
      (node (ref "VT7") (pin "3") (pinfunction "S_3") (pintype "passive"))
    )
    (net (code "36") (name "VCC_380V") (class "Default")
      (node (ref "C15") (pin "1") (pinfunction "1_1") (pintype "passive"))
      (node (ref "C9") (pin "1") (pinfunction "1_1") (pintype "passive"))
      (node (ref "R11") (pin "2") (pinfunction "2_2") (pintype "passive"))
      (node (ref "R22") (pin "2") (pinfunction "2_2") (pintype "passive"))
      (node (ref "VD10") (pin "2") (pinfunction "C_2") (pintype "passive"))
      (node (ref "VD3") (pin "2") (pinfunction "A_2") (pintype "passive"))
      (node (ref "VD5") (pin "2") (pinfunction "A_2") (pintype "passive"))
      (node (ref "VT5") (pin "2") (pinfunction "D_2") (pintype "passive"))
    )
    (net (code "37") (name "VCC_NONISO_12V0P") (class "Default")
      (node (ref "A1") (pin "1") (pinfunction "VCC_12V0_1") (pintype "passive"))
      (node (ref "C14") (pin "1") (pinfunction "1_1") (pintype "passive"))
      (node (ref "DA4") (pin "7") (pinfunction "VCC_7") (pintype "passive"))
      (node (ref "VT1") (pin "2") (pinfunction "C_2") (pintype "passive"))
      (node (ref "VT3") (pin "2") (pinfunction "C_2") (pintype "passive"))
    )
    (net (code "38") (name "unconnected-(A1-FB_CURRENT-Pad5)") (class "Default")
      (node (ref "A1") (pin "5") (pinfunction "FB_CURRENT_5") (pintype "input"))
    )
    (net (code "39") (name "unconnected-(A1-FB_VOLTAGE-Pad6)") (class "Default")
      (node (ref "A1") (pin "6") (pinfunction "FB_VOLTAGE_6") (pintype "input"))
    )
    (net (code "40") (name "unconnected-(A1-NC-Pad4)") (class "Default")
      (node (ref "A1") (pin "4") (pinfunction "NC_4") (pintype "passive+no_connect"))
    )
    (net (code "41") (name "unconnected-(A1-NC-Pad7)") (class "Default")
      (node (ref "A1") (pin "7") (pinfunction "NC_7") (pintype "passive+no_connect"))
    )
    (net (code "42") (name "unconnected-(A1-REF_5V0-Pad8)") (class "Default")
      (node (ref "A1") (pin "8") (pinfunction "REF_5V0_8") (pintype "passive+no_connect"))
    )
    (net (code "43") (name "unconnected-(DA1-ANODE-Pad1)") (class "Default")
      (node (ref "DA1") (pin "1") (pinfunction "ANODE_1") (pintype "passive"))
    )
    (net (code "44") (name "unconnected-(DA1-CATHODE-Pad2)") (class "Default")
      (node (ref "DA1") (pin "2") (pinfunction "CATHODE_2") (pintype "power_in"))
    )
    (net (code "45") (name "unconnected-(DA1-COLLECTOR-Pad4)") (class "Default")
      (node (ref "DA1") (pin "4") (pinfunction "COLLECTOR_4") (pintype "passive"))
    )
    (net (code "46") (name "unconnected-(DA1-EMITTER-Pad3)") (class "Default")
      (node (ref "DA1") (pin "3") (pinfunction "EMITTER_3") (pintype "passive"))
    )
    (net (code "47") (name "unconnected-(DA2-ANODE-Pad1)") (class "Default")
      (node (ref "DA2") (pin "1") (pinfunction "ANODE_1") (pintype "passive"))
    )
    (net (code "48") (name "unconnected-(DA2-CATHODE-Pad2)") (class "Default")
      (node (ref "DA2") (pin "2") (pinfunction "CATHODE_2") (pintype "power_in"))
    )
    (net (code "49") (name "unconnected-(DA2-COLLECTOR-Pad4)") (class "Default")
      (node (ref "DA2") (pin "4") (pinfunction "COLLECTOR_4") (pintype "passive"))
    )
    (net (code "50") (name "unconnected-(DA2-EMITTER-Pad3)") (class "Default")
      (node (ref "DA2") (pin "3") (pinfunction "EMITTER_3") (pintype "passive"))
    )
    (net (code "51") (name "unconnected-(DA3A-1IN+-Pad3)") (class "Default")
      (node (ref "DA3") (pin "3") (pinfunction "1IN+_3") (pintype "input"))
    )
    (net (code "52") (name "unconnected-(DA3A-1IN--Pad2)") (class "Default")
      (node (ref "DA3") (pin "2") (pinfunction "1IN-_2") (pintype "input"))
    )
    (net (code "53") (name "unconnected-(DA3A-1OUT-Pad1)") (class "Default")
      (node (ref "DA3") (pin "1") (pinfunction "1OUT_1") (pintype "output"))
    )
    (net (code "54") (name "unconnected-(DA3A-GND-Pad4)") (class "Default")
      (node (ref "DA3") (pin "4") (pinfunction "GND_4") (pintype "power_in"))
    )
    (net (code "55") (name "unconnected-(DA3A-VCC-Pad8)") (class "Default")
      (node (ref "DA3") (pin "8") (pinfunction "VCC_8") (pintype "power_in"))
    )
    (net (code "56") (name "unconnected-(DA3B-2IN+-Pad5)") (class "Default")
      (node (ref "DA3") (pin "5") (pinfunction "2IN+_5") (pintype "input"))
    )
    (net (code "57") (name "unconnected-(DA3B-2IN--Pad6)") (class "Default")
      (node (ref "DA3") (pin "6") (pinfunction "2IN-_6") (pintype "input"))
    )
    (net (code "58") (name "unconnected-(DA3B-2OUT-Pad7)") (class "Default")
      (node (ref "DA3") (pin "7") (pinfunction "2OUT_7") (pintype "output"))
    )
    (net (code "59") (name "unconnected-(FU1-Pad1)") (class "Default")
      (node (ref "FU1") (pin "1") (pinfunction "1_1") (pintype "passive"))
    )
    (net (code "60") (name "unconnected-(L6-Pad2)") (class "Default")
      (node (ref "L6") (pin "2") (pinfunction "2_2") (pintype "passive"))
    )
    (net (code "61") (name "unconnected-(R13-Pad1)") (class "Default")
      (node (ref "R13") (pin "1") (pinfunction "1_1") (pintype "passive"))
    )
    (net (code "62") (name "unconnected-(R13-Pad2)") (class "Default")
      (node (ref "R13") (pin "2") (pinfunction "2_2") (pintype "passive"))
    )
    (net (code "63") (name "unconnected-(R14-Pad1)") (class "Default")
      (node (ref "R14") (pin "1") (pinfunction "1_1") (pintype "passive"))
    )
    (net (code "64") (name "unconnected-(R14-Pad2)") (class "Default")
      (node (ref "R14") (pin "2") (pinfunction "2_2") (pintype "passive"))
    )
    (net (code "65") (name "unconnected-(R20-Pad1)") (class "Default")
      (node (ref "R20") (pin "1") (pinfunction "1_1") (pintype "passive"))
    )
    (net (code "66") (name "unconnected-(R20-Pad2)") (class "Default")
      (node (ref "R20") (pin "2") (pinfunction "2_2") (pintype "passive"))
    )
    (net (code "67") (name "unconnected-(RT1-Pad1)") (class "Default")
      (node (ref "RT1") (pin "1") (pinfunction "1_1") (pintype "passive"))
    )
    (net (code "68") (name "unconnected-(T1-Pad3)") (class "Default")
      (node (ref "T1") (pin "3") (pinfunction "3_3") (pintype "passive+no_connect"))
    )
    (net (code "69") (name "unconnected-(T1-Pad6)") (class "Default")
      (node (ref "T1") (pin "6") (pinfunction "6_6") (pintype "passive"))
    )
  )
)
